# circuit_Diagram.net
KiCad netlist of a schematic drawn in Altium Designer
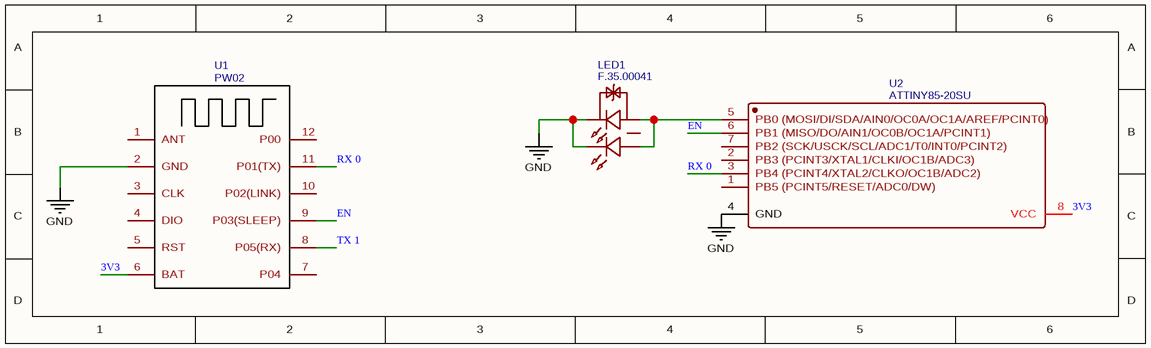
[diagram p0: circuit_Diagram.schdoc]

(export (version "E")
  (design (tool "Eeschema 10.0.6"))
  (components
    (comp (ref "LED1")
      (value "F.35.00041")
      (fields (field (name "BOM_SUPPLIER PART") "C909692") (field (name "CONTRIBUTOR") "LCSC"))
      (libsource (lib "altium-import") (part "root_2_F.35.00041_"))
    )
    (comp (ref "U1")
      (value "PW02")
      (fields (field (name "CONTRIBUTOR") "jzy1115"))
      (libsource (lib "altium-import") (part "root_0_PW02_"))
    )
    (comp (ref "U2")
      (value "ATTINY85-20SU")
      (fields (field (name "BOM_SUPPLIER PART") "C89852"))
      (libsource (lib "altium-import") (part "root_0_ATTINY85-20SU_"))
    )
  )
  (nets
    (net (code "1") (name "/3V3") (class "Default")
      (node (ref "U1") (pin "6") (pinfunction "BAT_6") (pintype "passive"))
      (node (ref "U2") (pin "8") (pinfunction "VCC_8") (pintype "passive"))
    )
    (net (code "2") (name "/EN") (class "Default")
      (node (ref "U1") (pin "9") (pinfunction "P03(SLEEP)_9") (pintype "passive"))
      (node (ref "U2") (pin "6") (pinfunction "PB1_(MISO/DO/AIN1/OC0B/OC1A/PCINT1)_6") (pintype "passive"))
    )
    (net (code "3") (name "/RX 0") (class "Default")
      (node (ref "U1") (pin "11") (pinfunction "P01(TX)_11") (pintype "passive"))
      (node (ref "U2") (pin "3") (pinfunction "PB4_(PCINT4/XTAL2/CLKO/OC1B/ADC2)_3") (pintype "passive"))
    )
    (net (code "4") (name "/TX 1") (class "Default")
      (node (ref "U1") (pin "8") (pinfunction "P05(RX)_8") (pintype "passive"))
    )
    (net (code "5") (name "GND") (class "Default")
      (node (ref "LED1") (pin "2") (pinfunction "UVA-_2") (pintype "passive"))
      (node (ref "LED1") (pin "4") (pinfunction "UVC-_4") (pintype "passive"))
      (node (ref "U1") (pin "2") (pinfunction "GND_2") (pintype "passive"))
      (node (ref "U2") (pin "4") (pinfunction "GND_4") (pintype "passive"))
    )
    (net (code "6") (name "Net-(LED1-UVA+)") (class "Default")
      (node (ref "LED1") (pin "1") (pinfunction "UVA+_1") (pintype "passive"))
      (node (ref "LED1") (pin "3") (pinfunction "UVC+_3") (pintype "passive"))
      (node (ref "U2") (pin "5") (pinfunction "PB0_(MOSI/DI/SDA/AIN0/OC0A/OC1A/AREF/PCINT0)_5") (pintype "passive"))
    )
    (net (code "7") (name "unconnected-(LED1-EP-Pad5)") (class "Default")
      (node (ref "LED1") (pin "5") (pinfunction "EP_5") (pintype "passive"))
    )
    (net (code "8") (name "unconnected-(U1-ANT-Pad1)") (class "Default")
      (node (ref "U1") (pin "1") (pinfunction "ANT_1") (pintype "passive"))
    )
    (net (code "9") (name "unconnected-(U1-CLK-Pad3)") (class "Default")
      (node (ref "U1") (pin "3") (pinfunction "CLK_3") (pintype "passive"))
    )
    (net (code "10") (name "unconnected-(U1-DIO-Pad4)") (class "Default")
      (node (ref "U1") (pin "4") (pinfunction "DIO_4") (pintype "passive"))
    )
    (net (code "11") (name "unconnected-(U1-P00-Pad12)") (class "Default")
      (node (ref "U1") (pin "12") (pinfunction "P00_12") (pintype "passive"))
    )
    (net (code "12") (name "unconnected-(U1-P02(LINK)-Pad10)") (class "Default")
      (node (ref "U1") (pin "10") (pinfunction "P02(LINK)_10") (pintype "passive"))
    )
    (net (code "13") (name "unconnected-(U1-P04-Pad7)") (class "Default")
      (node (ref "U1") (pin "7") (pinfunction "P04_7") (pintype "passive"))
    )
    (net (code "14") (name "unconnected-(U1-RST-Pad5)") (class "Default")
      (node (ref "U1") (pin "5") (pinfunction "RST_5") (pintype "passive"))
    )
    (net (code "15") (name "unconnected-(U2-PB2_(SCK{slash}USCK{slash}SCL{slash}ADC1{slash}T0{slash}INT0{slash}PCINT2)-Pad7)") (class "Default")
      (node (ref "U2") (pin "7") (pinfunction "PB2_(SCK/USCK/SCL/ADC1/T0/INT0/PCINT2)_7") (pintype "passive"))
    )
    (net (code "16") (name "unconnected-(U2-PB3_(PCINT3{slash}XTAL1{slash}CLKI{slash}OC1B{slash}ADC3)-Pad2)") (class "Default")
      (node (ref "U2") (pin "2") (pinfunction "PB3_(PCINT3/XTAL1/CLKI/OC1B/ADC3)_2") (pintype "passive"))
    )
    (net (code "17") (name "unconnected-(U2-PB5_(PCINT5{slash}RESET{slash}ADC0{slash}DW)-Pad1)") (class "Default")
      (node (ref "U2") (pin "1") (pinfunction "PB5_(PCINT5/RESET/ADC0/DW)_1") (pintype "passive"))
    )
  )
)
